# HandiFinder.net
KiCad netlist of a schematic drawn in EAGLE
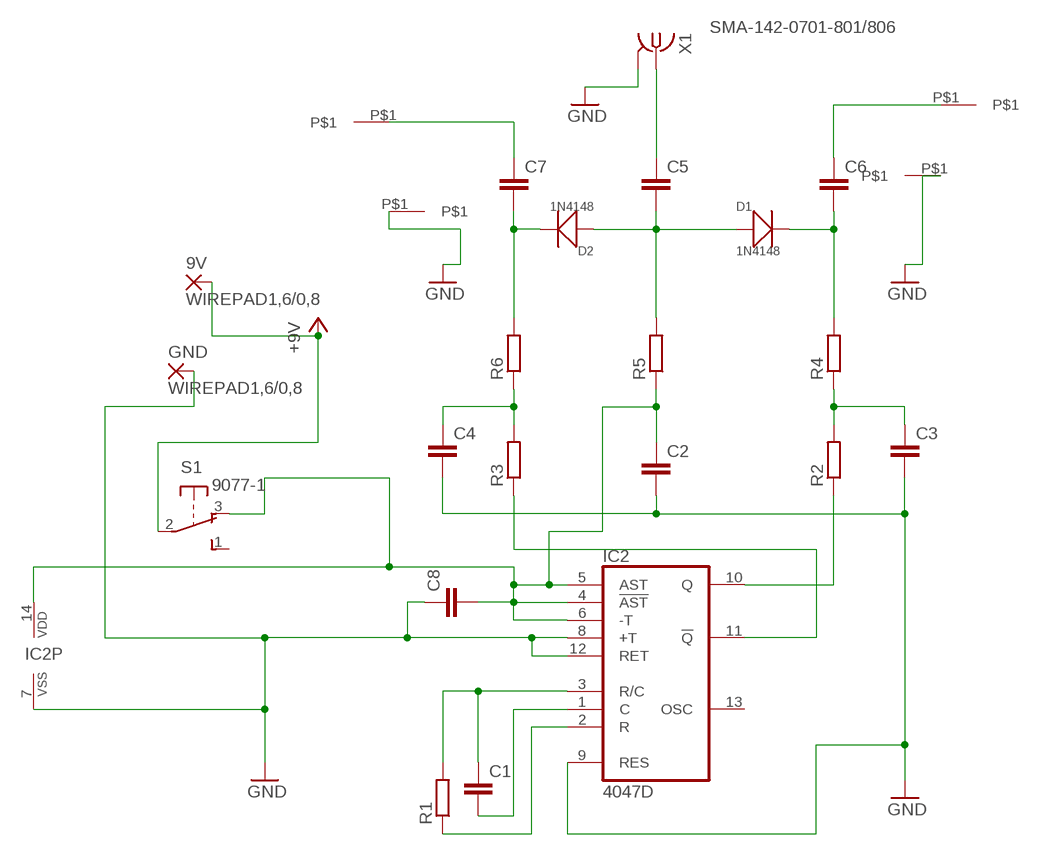
[diagram p0: schematic, sheet 1]

(export (version "E")
  (design (tool "Eeschema 10.0.6"))
  (components
    (comp (ref "9V")
      (value "WIREPAD1,6/0,8")
      (footprint "eagle-import:1,6_0,8")
      (libsource (lib "eagle-import") (part "WIREPAD1,6/0,8"))
    )
    (comp (ref "ANT1")
      (value "ANT12")
      (footprint "eagle-import:2.6MMHOLE")
      (libsource (lib "eagle-import") (part "WIREPAD"))
    )
    (comp (ref "ANT1GND2")
      (value "WIREPAD")
      (footprint "eagle-import:2.6MMHOLE")
      (libsource (lib "eagle-import") (part "WIREPAD"))
    )
    (comp (ref "ANT2GND2")
      (value "WIREPAD")
      (footprint "eagle-import:2.6MMHOLE")
      (libsource (lib "eagle-import") (part "WIREPAD"))
    )
    (comp (ref "ANT22")
      (value "WIREPAD")
      (footprint "eagle-import:2.6MMHOLE")
      (libsource (lib "eagle-import") (part "WIREPAD"))
    )
    (comp (ref "C1")
      (value "C-EUC0805K")
      (footprint "eagle-import:C0805K")
      (libsource (lib "eagle-import") (part "C-EUC0805K"))
    )
    (comp (ref "C2")
      (value "C-EUC0805K")
      (footprint "eagle-import:C0805K")
      (libsource (lib "eagle-import") (part "C-EUC0805K"))
    )
    (comp (ref "C3")
      (value "C-EUC0805K")
      (footprint "eagle-import:C0805K")
      (libsource (lib "eagle-import") (part "C-EUC0805K"))
    )
    (comp (ref "C4")
      (value "C-EUC0805K")
      (footprint "eagle-import:C0805K")
      (libsource (lib "eagle-import") (part "C-EUC0805K"))
    )
    (comp (ref "C5")
      (value "C-EUC0805K")
      (footprint "eagle-import:C0805K")
      (libsource (lib "eagle-import") (part "C-EUC0805K"))
    )
    (comp (ref "C6")
      (value "C-EUC0805K")
      (footprint "eagle-import:C0805K")
      (libsource (lib "eagle-import") (part "C-EUC0805K"))
    )
    (comp (ref "C7")
      (value "C-EUC0805K")
      (footprint "eagle-import:C0805K")
      (libsource (lib "eagle-import") (part "C-EUC0805K"))
    )
    (comp (ref "C8")
      (value "C-EUC0805K")
      (footprint "eagle-import:C0805K")
      (libsource (lib "eagle-import") (part "C-EUC0805K"))
    )
    (comp (ref "D1")
      (value "1N4148")
      (footprint "eagle-import:SOD-123")
      (fields (field (name "MPN") "MMSD4148"))
      (libsource (lib "eagle-import") (part "SMD-DIODE-100V-200MA(SOD-123)"))
    )
    (comp (ref "D2")
      (value "1N4148")
      (footprint "eagle-import:SOD-123")
      (fields (field (name "MPN") "MMSD4148"))
      (libsource (lib "eagle-import") (part "SMD-DIODE-100V-200MA(SOD-123)"))
    )
    (comp (ref "GND")
      (value "WIREPAD1,6/0,8")
      (footprint "eagle-import:1,6_0,8")
      (libsource (lib "eagle-import") (part "WIREPAD1,6/0,8"))
    )
    (comp (ref "IC2")
      (value "4047D")
      (footprint "eagle-import:SO14")
      (libsource (lib "eagle-import") (part "4047D"))
    )
    (comp (ref "R1")
      (value "R-EU_R0805")
      (footprint "eagle-import:R0805")
      (libsource (lib "eagle-import") (part "R-EU_R0805"))
    )
    (comp (ref "R2")
      (value "R-EU_R0805")
      (footprint "eagle-import:R0805")
      (libsource (lib "eagle-import") (part "R-EU_R0805"))
    )
    (comp (ref "R3")
      (value "R-EU_R0805")
      (footprint "eagle-import:R0805")
      (libsource (lib "eagle-import") (part "R-EU_R0805"))
    )
    (comp (ref "R4")
      (value "R-EU_R0805")
      (footprint "eagle-import:R0805")
      (libsource (lib "eagle-import") (part "R-EU_R0805"))
    )
    (comp (ref "R5")
      (value "R-EU_R0805")
      (footprint "eagle-import:R0805")
      (libsource (lib "eagle-import") (part "R-EU_R0805"))
    )
    (comp (ref "R6")
      (value "R-EU_R0805")
      (footprint "eagle-import:R0805")
      (libsource (lib "eagle-import") (part "R-EU_R0805"))
    )
    (comp (ref "S1")
      (value "9077-1")
      (footprint "eagle-import:9077-1")
      (libsource (lib "eagle-import") (part "9077-1"))
    )
    (comp (ref "X1")
      (value "SMA-142-0701-801/806")
      (footprint "eagle-import:J502-ND-142-0701-801_806")
      (fields (field (name "MF") "JOHNSON COMPONENTS") (field (name "MPN") "142-0701-801"))
      (libsource (lib "eagle-import") (part "SMA-142-0701-801/806"))
    )
  )
  (nets
    (net (code "1") (name "+9V") (class "Default")
      (node (ref "9V") (pin "1") (pinfunction "P_1") (pintype "passive"))
      (node (ref "S1") (pin "2") (pinfunction "P_2") (pintype "passive"))
    )
    (net (code "2") (name "GND") (class "Default")
      (node (ref "ANT1GND2") (pin "P$1") (pinfunction "P$1_P$1") (pintype "bidirectional"))
      (node (ref "ANT2GND2") (pin "P$1") (pinfunction "P$1_P$1") (pintype "bidirectional"))
      (node (ref "C2") (pin "2") (pinfunction "2_2") (pintype "passive"))
      (node (ref "C3") (pin "2") (pinfunction "2_2") (pintype "passive"))
      (node (ref "C4") (pin "2") (pinfunction "2_2") (pintype "passive"))
      (node (ref "C8") (pin "1") (pinfunction "1_1") (pintype "passive"))
      (node (ref "GND") (pin "1") (pinfunction "P_1") (pintype "passive"))
      (node (ref "IC2") (pin "12") (pinfunction "RET_12") (pintype "input"))
      (node (ref "IC2") (pin "7") (pinfunction "VSS_7") (pintype "power_in"))
      (node (ref "IC2") (pin "8") (pinfunction "+T_8") (pintype "input"))
      (node (ref "IC2") (pin "9") (pinfunction "RES_9") (pintype "input"))
      (node (ref "X1") (pin "G@1") (pinfunction "2_G@1") (pintype "passive"))
      (node (ref "X1") (pin "G@2") (pinfunction "2_G@2") (pintype "passive"))
      (node (ref "X1") (pin "G@3") (pinfunction "2_G@3") (pintype "passive"))
      (node (ref "X1") (pin "G@4") (pinfunction "2_G@4") (pintype "passive"))
    )
    (net (code "3") (name "Net-(ANT1-PadP$1)") (class "Default")
      (node (ref "ANT1") (pin "P$1") (pinfunction "P$1_P$1") (pintype "bidirectional"))
      (node (ref "C7") (pin "1") (pinfunction "1_1") (pintype "passive"))
    )
    (net (code "4") (name "Net-(ANT22-PadP$1)") (class "Default")
      (node (ref "ANT22") (pin "P$1") (pinfunction "P$1_P$1") (pintype "bidirectional"))
      (node (ref "C6") (pin "1") (pinfunction "1_1") (pintype "passive"))
    )
    (net (code "5") (name "Net-(C3-Pad1)") (class "Default")
      (node (ref "C3") (pin "1") (pinfunction "1_1") (pintype "passive"))
      (node (ref "R2") (pin "2") (pinfunction "2_2") (pintype "passive"))
      (node (ref "R4") (pin "1") (pinfunction "1_1") (pintype "passive"))
    )
    (net (code "6") (name "Net-(C4-Pad1)") (class "Default")
      (node (ref "C4") (pin "1") (pinfunction "1_1") (pintype "passive"))
      (node (ref "R3") (pin "2") (pinfunction "2_2") (pintype "passive"))
      (node (ref "R6") (pin "1") (pinfunction "1_1") (pintype "passive"))
    )
    (net (code "7") (name "Net-(C5-Pad1)") (class "Default")
      (node (ref "C5") (pin "1") (pinfunction "1_1") (pintype "passive"))
      (node (ref "X1") (pin "1") (pinfunction "1_1") (pintype "passive"))
    )
    (net (code "8") (name "Net-(C5-Pad2)") (class "Default")
      (node (ref "C5") (pin "2") (pinfunction "2_2") (pintype "passive"))
      (node (ref "D1") (pin "+") (pinfunction "+_+") (pintype "passive"))
      (node (ref "D2") (pin "+") (pinfunction "+_+") (pintype "passive"))
      (node (ref "R5") (pin "2") (pinfunction "2_2") (pintype "passive"))
    )
    (net (code "9") (name "Net-(C6-Pad2)") (class "Default")
      (node (ref "C6") (pin "2") (pinfunction "2_2") (pintype "passive"))
      (node (ref "D1") (pin "-") (pinfunction "-_-") (pintype "passive"))
      (node (ref "R4") (pin "2") (pinfunction "2_2") (pintype "passive"))
    )
    (net (code "10") (name "Net-(C7-Pad2)") (class "Default")
      (node (ref "C7") (pin "2") (pinfunction "2_2") (pintype "passive"))
      (node (ref "D2") (pin "-") (pinfunction "-_-") (pintype "passive"))
      (node (ref "R6") (pin "2") (pinfunction "2_2") (pintype "passive"))
    )
    (net (code "11") (name "Net-(IC2A--T)") (class "Default")
      (node (ref "C2") (pin "1") (pinfunction "1_1") (pintype "passive"))
      (node (ref "C8") (pin "2") (pinfunction "2_2") (pintype "passive"))
      (node (ref "IC2") (pin "14") (pinfunction "VDD_14") (pintype "power_in"))
      (node (ref "IC2") (pin "4") (pinfunction "~{AST}_4") (pintype "input"))
      (node (ref "IC2") (pin "5") (pinfunction "AST_5") (pintype "input"))
      (node (ref "IC2") (pin "6") (pinfunction "-T_6") (pintype "input"))
      (node (ref "R5") (pin "1") (pinfunction "1_1") (pintype "passive"))
      (node (ref "S1") (pin "3") (pinfunction "O_3") (pintype "passive"))
    )
    (net (code "12") (name "Net-(IC2A-C)") (class "Default")
      (node (ref "C1") (pin "2") (pinfunction "2_2") (pintype "passive"))
      (node (ref "IC2") (pin "1") (pinfunction "C_1") (pintype "input"))
    )
    (net (code "13") (name "Net-(IC2A-Q)") (class "Default")
      (node (ref "IC2") (pin "10") (pinfunction "Q_10") (pintype "output"))
      (node (ref "R2") (pin "1") (pinfunction "1_1") (pintype "passive"))
    )
    (net (code "14") (name "Net-(IC2A-R)") (class "Default")
      (node (ref "IC2") (pin "2") (pinfunction "R_2") (pintype "input"))
      (node (ref "R1") (pin "1") (pinfunction "1_1") (pintype "passive"))
    )
    (net (code "15") (name "Net-(IC2A-R{slash}C)") (class "Default")
      (node (ref "C1") (pin "1") (pinfunction "1_1") (pintype "passive"))
      (node (ref "IC2") (pin "3") (pinfunction "R/C_3") (pintype "input"))
      (node (ref "R1") (pin "2") (pinfunction "2_2") (pintype "passive"))
    )
    (net (code "16") (name "Net-(IC2A-~{Q})") (class "Default")
      (node (ref "IC2") (pin "11") (pinfunction "~{Q}_11") (pintype "output"))
      (node (ref "R3") (pin "1") (pinfunction "1_1") (pintype "passive"))
    )
    (net (code "17") (name "unconnected-(IC2A-OSC-Pad13)") (class "Default")
      (node (ref "IC2") (pin "13") (pinfunction "OSC_13") (pintype "output"))
    )
    (net (code "18") (name "unconnected-(S1-S-Pad1)") (class "Default")
      (node (ref "S1") (pin "1") (pinfunction "S_1") (pintype "passive"))
    )
  )
)
